# window.net
KiCad netlist of a schematic drawn in EAGLE
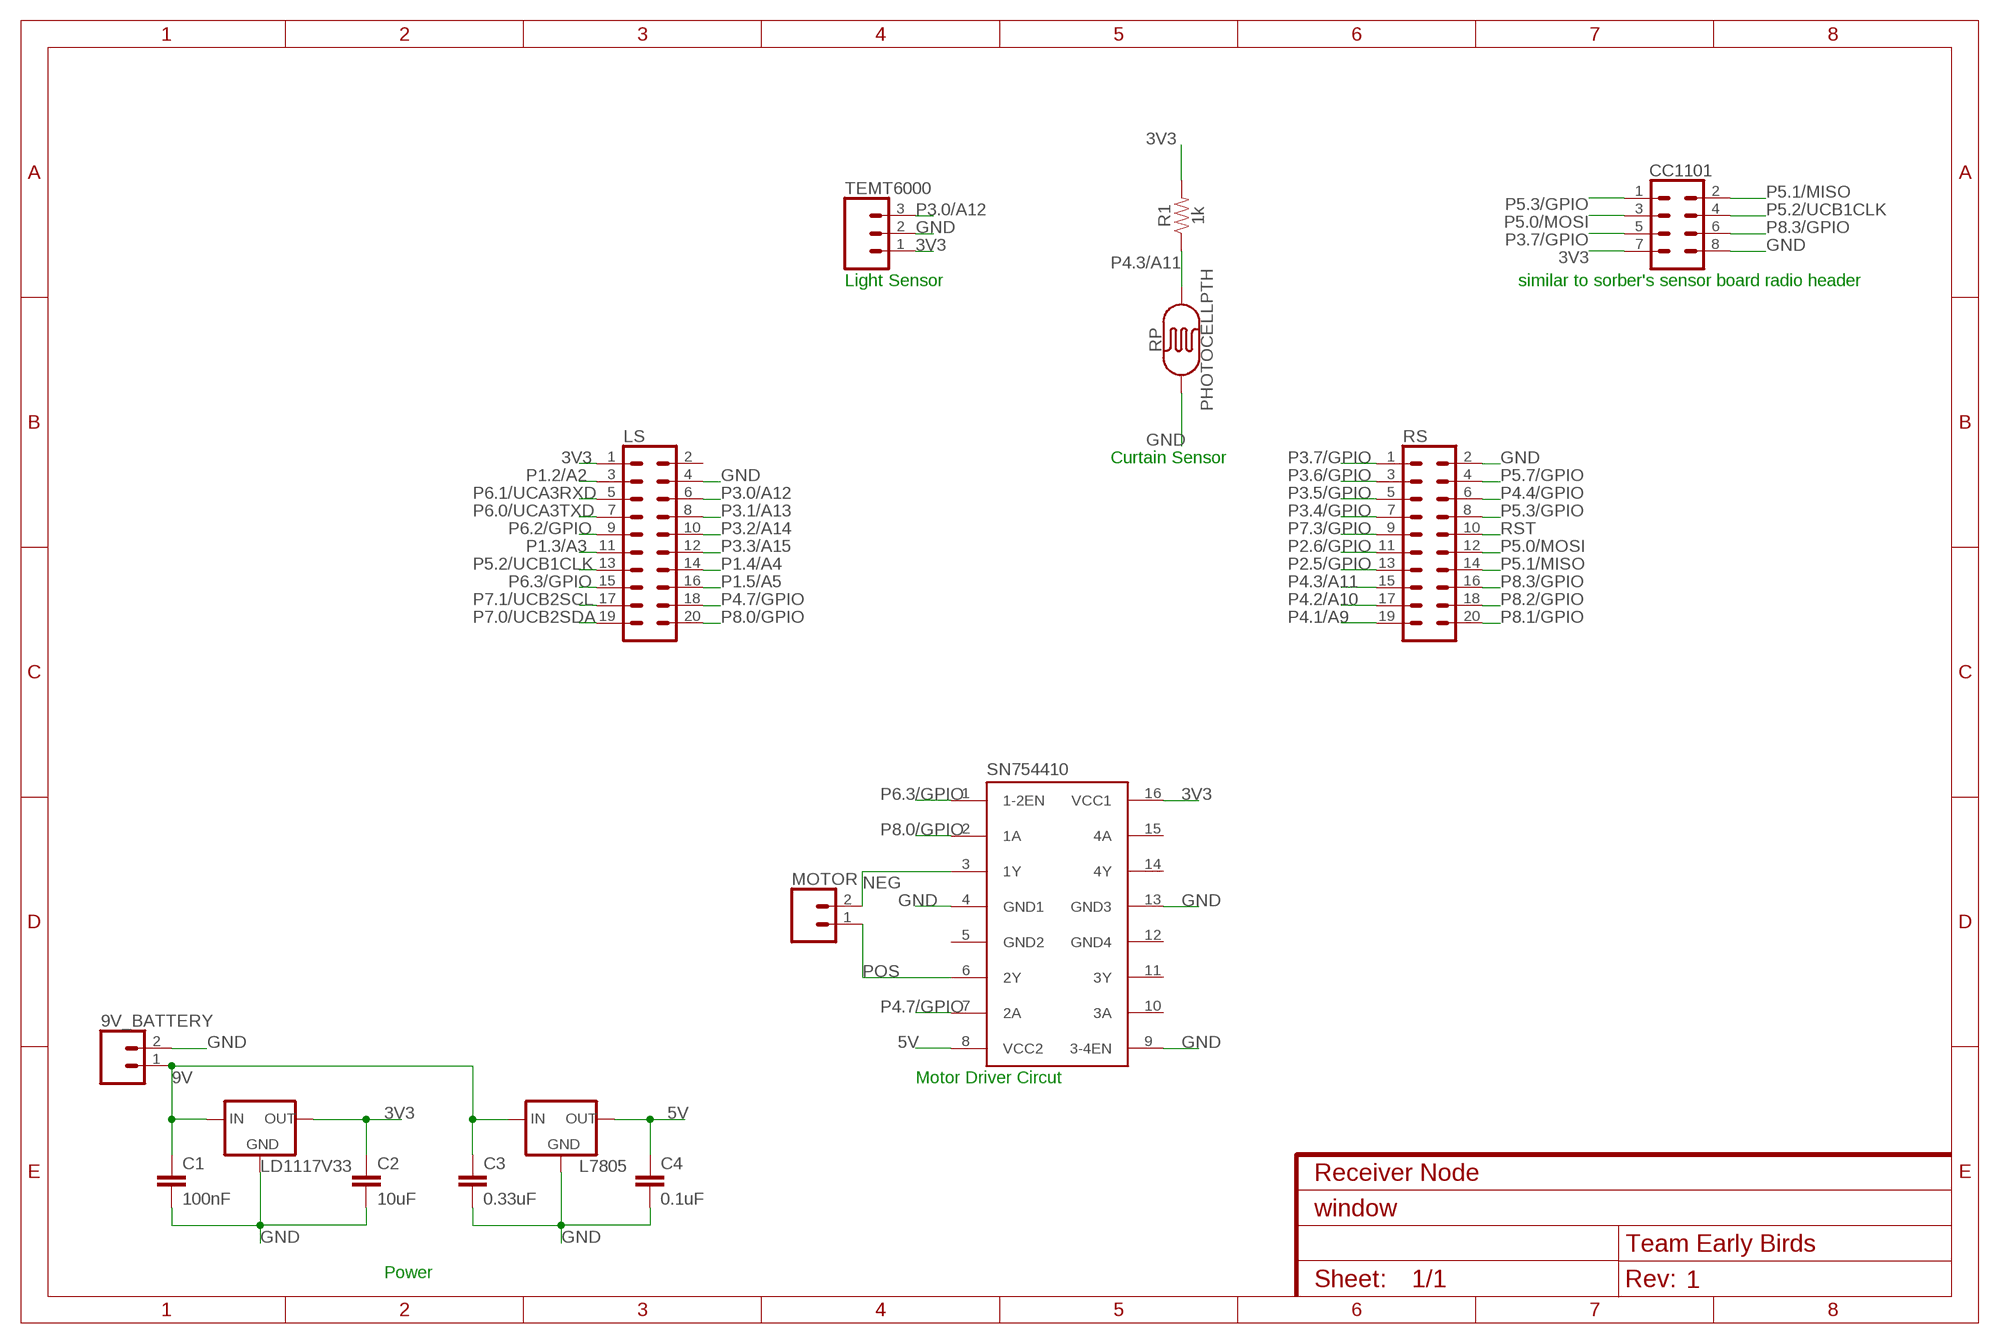
[diagram p0: schematic, sheet 1]

(export (version "E")
  (design (tool "Eeschema 10.0.6"))
  (components
    (comp (ref "9V_BATTERY")
      (value "CONN_02")
      (footprint "eagle-import:1X02")
      (libsource (lib "eagle-import") (part "CONN_02"))
    )
    (comp (ref "C1")
      (value "100nF")
      (footprint "eagle-import:C0805")
      (libsource (lib "eagle-import") (part "C-EUC0805"))
    )
    (comp (ref "C2")
      (value "10uF")
      (footprint "eagle-import:C0805")
      (libsource (lib "eagle-import") (part "C-EUC0805"))
    )
    (comp (ref "C3")
      (value "0.33uF")
      (footprint "eagle-import:C0805")
      (libsource (lib "eagle-import") (part "C-EUC0805"))
    )
    (comp (ref "C4")
      (value "0.1uF")
      (footprint "eagle-import:C0805")
      (libsource (lib "eagle-import") (part "C-EUC0805"))
    )
    (comp (ref "CC1101")
      (value "CONN_04X2")
      (footprint "eagle-import:2X4")
      (libsource (lib "eagle-import") (part "CONN_04X2"))
    )
    (comp (ref "L7805")
      (value "V_REG_78XX-TO-220")
      (footprint "eagle-import:TO-220-ALT")
      (libsource (lib "eagle-import") (part "V_REG_78XX-TO-220"))
    )
    (comp (ref "LD1117V33")
      (value "V_REG_LD1117VXX")
      (footprint "eagle-import:TO-220-ALT2")
      (libsource (lib "eagle-import") (part "V_REG_LD1117VXX"))
    )
    (comp (ref "LS")
      (value "CONN_10X2")
      (footprint "eagle-import:2X10")
      (libsource (lib "eagle-import") (part "CONN_10X2"))
    )
    (comp (ref "MOTOR")
      (value "CONN_02")
      (footprint "eagle-import:1X02")
      (libsource (lib "eagle-import") (part "CONN_02"))
    )
    (comp (ref "R1")
      (value "1k")
      (footprint "eagle-import:AXIAL-0.3")
      (libsource (lib "eagle-import") (part "1KOHM-HORIZ-1/4W-1%"))
    )
    (comp (ref "RP")
      (value "PHOTOCELLPTH")
      (footprint "eagle-import:PHOTOCELL")
      (libsource (lib "eagle-import") (part "PHOTOCELLPTH"))
    )
    (comp (ref "RS")
      (value "CONN_10X2")
      (footprint "eagle-import:2X10")
      (libsource (lib "eagle-import") (part "CONN_10X2"))
    )
    (comp (ref "SN754410")
      (value "L293D")
      (footprint "eagle-import:DIL16")
      (libsource (lib "eagle-import") (part "L293D"))
    )
    (comp (ref "TEMT6000")
      (value "455-1750-1-ND")
      (footprint "eagle-import:1X03")
      (libsource (lib "eagle-import") (part "CONN_03"))
    )
  )
  (nets
    (net (code "1") (name "/3V3") (class "Default")
      (node (ref "C2") (pin "1") (pinfunction "1_1") (pintype "passive"))
      (node (ref "CC1101") (pin "7") (pinfunction "7_7") (pintype "passive"))
      (node (ref "LD1117V33") (pin "OUT") (pinfunction "OUT_OUT") (pintype "passive"))
      (node (ref "LS") (pin "1") (pinfunction "1_1") (pintype "passive"))
      (node (ref "R1") (pin "P$2") (pinfunction "2_P$2") (pintype "passive"))
      (node (ref "SN754410") (pin "16") (pinfunction "VCC1_16") (pintype "power_in"))
      (node (ref "TEMT6000") (pin "1") (pinfunction "1_1") (pintype "passive"))
    )
    (net (code "2") (name "/5V") (class "Default")
      (node (ref "C4") (pin "1") (pinfunction "1_1") (pintype "passive"))
      (node (ref "L7805") (pin "OUT") (pinfunction "OUT_OUT") (pintype "passive"))
      (node (ref "SN754410") (pin "8") (pinfunction "VCC2_8") (pintype "power_in"))
    )
    (net (code "3") (name "/9V") (class "Default")
      (node (ref "9V_BATTERY") (pin "1") (pinfunction "1_1") (pintype "passive"))
      (node (ref "C1") (pin "1") (pinfunction "1_1") (pintype "passive"))
      (node (ref "C3") (pin "1") (pinfunction "1_1") (pintype "passive"))
      (node (ref "L7805") (pin "IN") (pinfunction "IN_IN") (pintype "input"))
      (node (ref "LD1117V33") (pin "IN") (pinfunction "IN_IN") (pintype "input"))
    )
    (net (code "4") (name "/GND") (class "Default")
      (node (ref "9V_BATTERY") (pin "2") (pinfunction "2_2") (pintype "passive"))
      (node (ref "C1") (pin "2") (pinfunction "2_2") (pintype "passive"))
      (node (ref "C2") (pin "2") (pinfunction "2_2") (pintype "passive"))
      (node (ref "C3") (pin "2") (pinfunction "2_2") (pintype "passive"))
      (node (ref "C4") (pin "2") (pinfunction "2_2") (pintype "passive"))
      (node (ref "CC1101") (pin "8") (pinfunction "8_8") (pintype "passive"))
      (node (ref "L7805") (pin "GND") (pinfunction "GND_GND") (pintype "input"))
      (node (ref "LD1117V33") (pin "GND") (pinfunction "GND_GND") (pintype "input"))
      (node (ref "LS") (pin "4") (pinfunction "4_4") (pintype "passive"))
      (node (ref "RP") (pin "1") (pinfunction "P$1_1") (pintype "bidirectional"))
      (node (ref "RS") (pin "2") (pinfunction "2_2") (pintype "passive"))
      (node (ref "SN754410") (pin "13") (pinfunction "GND3_13") (pintype "power_in"))
      (node (ref "SN754410") (pin "4") (pinfunction "GND1_4") (pintype "power_in"))
      (node (ref "SN754410") (pin "9") (pinfunction "3-4EN_9") (pintype "input"))
      (node (ref "TEMT6000") (pin "2") (pinfunction "2_2") (pintype "passive"))
    )
    (net (code "5") (name "/GND2") (class "Default")
      (node (ref "SN754410") (pin "5") (pinfunction "GND2_5") (pintype "power_in"))
    )
    (net (code "6") (name "/GND4") (class "Default")
      (node (ref "SN754410") (pin "12") (pinfunction "GND4_12") (pintype "power_in"))
    )
    (net (code "7") (name "/NEG") (class "Default")
      (node (ref "MOTOR") (pin "2") (pinfunction "2_2") (pintype "passive"))
      (node (ref "SN754410") (pin "3") (pinfunction "1Y_3") (pintype "output"))
    )
    (net (code "8") (name "/P1.2{slash}A2") (class "Default")
      (node (ref "LS") (pin "3") (pinfunction "3_3") (pintype "passive"))
    )
    (net (code "9") (name "/P1.3{slash}A3") (class "Default")
      (node (ref "LS") (pin "11") (pinfunction "11_11") (pintype "passive"))
    )
    (net (code "10") (name "/P1.4{slash}A4") (class "Default")
      (node (ref "LS") (pin "14") (pinfunction "14_14") (pintype "passive"))
    )
    (net (code "11") (name "/P1.5{slash}A5") (class "Default")
      (node (ref "LS") (pin "16") (pinfunction "16_16") (pintype "passive"))
    )
    (net (code "12") (name "/P2.5{slash}GPIO") (class "Default")
      (node (ref "RS") (pin "13") (pinfunction "13_13") (pintype "passive"))
    )
    (net (code "13") (name "/P2.6{slash}GPIO") (class "Default")
      (node (ref "RS") (pin "11") (pinfunction "11_11") (pintype "passive"))
    )
    (net (code "14") (name "/P3.0{slash}A12") (class "Default")
      (node (ref "LS") (pin "6") (pinfunction "6_6") (pintype "passive"))
      (node (ref "TEMT6000") (pin "3") (pinfunction "3_3") (pintype "passive"))
    )
    (net (code "15") (name "/P3.1{slash}A13") (class "Default")
      (node (ref "LS") (pin "8") (pinfunction "8_8") (pintype "passive"))
    )
    (net (code "16") (name "/P3.2{slash}A14") (class "Default")
      (node (ref "LS") (pin "10") (pinfunction "10_10") (pintype "passive"))
    )
    (net (code "17") (name "/P3.3{slash}A15") (class "Default")
      (node (ref "LS") (pin "12") (pinfunction "12_12") (pintype "passive"))
    )
    (net (code "18") (name "/P3.4{slash}GPIO") (class "Default")
      (node (ref "RS") (pin "7") (pinfunction "7_7") (pintype "passive"))
    )
    (net (code "19") (name "/P3.5{slash}GPIO") (class "Default")
      (node (ref "RS") (pin "5") (pinfunction "5_5") (pintype "passive"))
    )
    (net (code "20") (name "/P3.6{slash}GPIO") (class "Default")
      (node (ref "RS") (pin "3") (pinfunction "3_3") (pintype "passive"))
    )
    (net (code "21") (name "/P3.7{slash}GPIO") (class "Default")
      (node (ref "CC1101") (pin "5") (pinfunction "5_5") (pintype "passive"))
      (node (ref "RS") (pin "1") (pinfunction "1_1") (pintype "passive"))
    )
    (net (code "22") (name "/P4.1{slash}A9") (class "Default")
      (node (ref "RS") (pin "19") (pinfunction "19_19") (pintype "passive"))
    )
    (net (code "23") (name "/P4.2{slash}A10") (class "Default")
      (node (ref "RS") (pin "17") (pinfunction "17_17") (pintype "passive"))
    )
    (net (code "24") (name "/P4.3{slash}A11") (class "Default")
      (node (ref "R1") (pin "P$1") (pinfunction "1_P$1") (pintype "passive"))
      (node (ref "RP") (pin "2") (pinfunction "P$2_2") (pintype "bidirectional"))
      (node (ref "RS") (pin "15") (pinfunction "15_15") (pintype "passive"))
    )
    (net (code "25") (name "/P4.4{slash}GPIO") (class "Default")
      (node (ref "RS") (pin "6") (pinfunction "6_6") (pintype "passive"))
    )
    (net (code "26") (name "/P4.7{slash}GPIO") (class "Default")
      (node (ref "LS") (pin "18") (pinfunction "18_18") (pintype "passive"))
      (node (ref "SN754410") (pin "7") (pinfunction "2A_7") (pintype "input"))
    )
    (net (code "27") (name "/P5.0{slash}MOSI") (class "Default")
      (node (ref "CC1101") (pin "3") (pinfunction "3_3") (pintype "passive"))
      (node (ref "RS") (pin "12") (pinfunction "12_12") (pintype "passive"))
    )
    (net (code "28") (name "/P5.1{slash}MISO") (class "Default")
      (node (ref "CC1101") (pin "2") (pinfunction "2_2") (pintype "passive"))
      (node (ref "RS") (pin "14") (pinfunction "14_14") (pintype "passive"))
    )
    (net (code "29") (name "/P5.2{slash}UCB1CLK") (class "Default")
      (node (ref "CC1101") (pin "4") (pinfunction "4_4") (pintype "passive"))
      (node (ref "LS") (pin "13") (pinfunction "13_13") (pintype "passive"))
    )
    (net (code "30") (name "/P5.3{slash}GPIO") (class "Default")
      (node (ref "CC1101") (pin "1") (pinfunction "1_1") (pintype "passive"))
      (node (ref "RS") (pin "8") (pinfunction "8_8") (pintype "passive"))
    )
    (net (code "31") (name "/P5.7{slash}GPIO") (class "Default")
      (node (ref "RS") (pin "4") (pinfunction "4_4") (pintype "passive"))
    )
    (net (code "32") (name "/P6.0{slash}UCA3TXD") (class "Default")
      (node (ref "LS") (pin "7") (pinfunction "7_7") (pintype "passive"))
    )
    (net (code "33") (name "/P6.1{slash}UCA3RXD") (class "Default")
      (node (ref "LS") (pin "5") (pinfunction "5_5") (pintype "passive"))
    )
    (net (code "34") (name "/P6.2{slash}GPIO") (class "Default")
      (node (ref "LS") (pin "9") (pinfunction "9_9") (pintype "passive"))
    )
    (net (code "35") (name "/P6.3{slash}GPIO") (class "Default")
      (node (ref "LS") (pin "15") (pinfunction "15_15") (pintype "passive"))
      (node (ref "SN754410") (pin "1") (pinfunction "1-2EN_1") (pintype "input"))
    )
    (net (code "36") (name "/P7.0{slash}UCB2SDA") (class "Default")
      (node (ref "LS") (pin "19") (pinfunction "19_19") (pintype "passive"))
    )
    (net (code "37") (name "/P7.1{slash}UCB2SCL") (class "Default")
      (node (ref "LS") (pin "17") (pinfunction "17_17") (pintype "passive"))
    )
    (net (code "38") (name "/P7.3{slash}GPIO") (class "Default")
      (node (ref "RS") (pin "9") (pinfunction "9_9") (pintype "passive"))
    )
    (net (code "39") (name "/P8.0{slash}GPIO") (class "Default")
      (node (ref "LS") (pin "20") (pinfunction "20_20") (pintype "passive"))
      (node (ref "SN754410") (pin "2") (pinfunction "1A_2") (pintype "input"))
    )
    (net (code "40") (name "/P8.1{slash}GPIO") (class "Default")
      (node (ref "RS") (pin "20") (pinfunction "20_20") (pintype "passive"))
    )
    (net (code "41") (name "/P8.2{slash}GPIO") (class "Default")
      (node (ref "RS") (pin "18") (pinfunction "18_18") (pintype "passive"))
    )
    (net (code "42") (name "/P8.3{slash}GPIO") (class "Default")
      (node (ref "CC1101") (pin "6") (pinfunction "6_6") (pintype "passive"))
      (node (ref "RS") (pin "16") (pinfunction "16_16") (pintype "passive"))
    )
    (net (code "43") (name "/POS") (class "Default")
      (node (ref "MOTOR") (pin "1") (pinfunction "1_1") (pintype "passive"))
      (node (ref "SN754410") (pin "6") (pinfunction "2Y_6") (pintype "output"))
    )
    (net (code "44") (name "/RST") (class "Default")
      (node (ref "RS") (pin "10") (pinfunction "10_10") (pintype "passive"))
    )
    (net (code "45") (name "unconnected-(LS-Pad2)") (class "Default")
      (node (ref "LS") (pin "2") (pinfunction "2_2") (pintype "passive"))
    )
    (net (code "46") (name "unconnected-(SN754410-3A-Pad10)") (class "Default")
      (node (ref "SN754410") (pin "10") (pinfunction "3A_10") (pintype "input"))
    )
    (net (code "47") (name "unconnected-(SN754410-3Y-Pad11)") (class "Default")
      (node (ref "SN754410") (pin "11") (pinfunction "3Y_11") (pintype "output"))
    )
    (net (code "48") (name "unconnected-(SN754410-4A-Pad15)") (class "Default")
      (node (ref "SN754410") (pin "15") (pinfunction "4A_15") (pintype "input"))
    )
    (net (code "49") (name "unconnected-(SN754410-4Y-Pad14)") (class "Default")
      (node (ref "SN754410") (pin "14") (pinfunction "4Y_14") (pintype "output"))
    )
  )
)
